# switch.net
KiCad netlist of a schematic drawn in Altium Designer
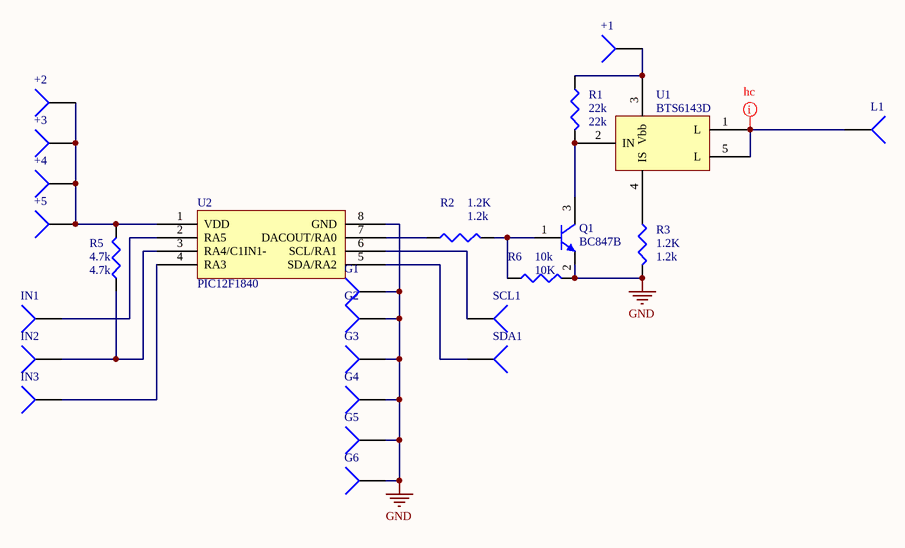
[diagram p0: switch.SchDoc]

(export (version "E")
  (design (tool "Eeschema 10.0.6"))
  (components
    (comp (ref "+1")
      (value "Socket")
      (footprint "PIN1")
      (fields (field (name "PUBLISHER") "Altium Limited"))
      (libsource (lib "misc") (part "Socket"))
    )
    (comp (ref "+2")
      (value "Socket")
      (footprint "PIN1L")
      (fields (field (name "PUBLISHER") "Altium Limited"))
      (libsource (lib "misc") (part "Socket"))
    )
    (comp (ref "+3")
      (value "Socket")
      (footprint "PIN1L")
      (fields (field (name "PUBLISHER") "Altium Limited"))
      (libsource (lib "misc") (part "Socket"))
    )
    (comp (ref "+4")
      (value "Socket")
      (footprint "PIN1L")
      (fields (field (name "PUBLISHER") "Altium Limited"))
      (libsource (lib "misc") (part "Socket"))
    )
    (comp (ref "+5")
      (value "Socket")
      (footprint "PIN1L")
      (fields (field (name "PUBLISHER") "Altium Limited"))
      (libsource (lib "misc") (part "Socket"))
    )
    (comp (ref "G1")
      (value "Socket")
      (footprint "PIN1L")
      (fields (field (name "PUBLISHER") "Altium Limited"))
      (libsource (lib "misc") (part "Socket"))
    )
    (comp (ref "G2")
      (value "Socket")
      (footprint "PIN1L")
      (fields (field (name "PUBLISHER") "Altium Limited"))
      (libsource (lib "misc") (part "Socket"))
    )
    (comp (ref "G3")
      (value "Socket")
      (footprint "PIN1L")
      (fields (field (name "PUBLISHER") "Altium Limited"))
      (libsource (lib "misc") (part "Socket"))
    )
    (comp (ref "G4")
      (value "Socket")
      (footprint "PIN1L")
      (fields (field (name "PUBLISHER") "Altium Limited"))
      (libsource (lib "misc") (part "Socket"))
    )
    (comp (ref "G5")
      (value "Socket")
      (footprint "PIN1")
      (fields (field (name "PUBLISHER") "Altium Limited"))
      (libsource (lib "misc") (part "Socket"))
    )
    (comp (ref "G6")
      (value "Socket")
      (footprint "PIN1")
      (fields (field (name "PUBLISHER") "Altium Limited"))
      (libsource (lib "misc") (part "Socket"))
    )
    (comp (ref "IN1")
      (value "Socket")
      (footprint "PIN1L")
      (fields (field (name "PUBLISHER") "Altium Limited"))
      (libsource (lib "misc") (part "Socket"))
    )
    (comp (ref "IN2")
      (value "Socket")
      (footprint "PIN1L")
      (fields (field (name "PUBLISHER") "Altium Limited"))
      (libsource (lib "misc") (part "Socket"))
    )
    (comp (ref "IN3")
      (value "Socket")
      (footprint "PIN1L")
      (fields (field (name "PUBLISHER") "Altium Limited"))
      (libsource (lib "misc") (part "Socket"))
    )
    (comp (ref "L1")
      (value "Socket")
      (footprint "PIN1")
      (fields (field (name "PUBLISHER") "Altium Limited"))
      (libsource (lib "misc") (part "Socket"))
    )
    (comp (ref "Q1")
      (value "BC847B")
      (footprint "SOT-23_N")
      (description "NPN Bipolar Transistor")
      (fields (field (name "PUBLISHER") "Altium Limited"))
      (libsource (lib "Miscellaneous Devices") (part "NPN"))
    )
    (comp (ref "R1")
      (value "22k")
      (footprint "J1-0603")
      (description "Resistor")
      (fields (field (name "ALTIUM_VALUE") "22k") (field (name "PUBLISHER") "Altium Limited"))
      (libsource (lib "Miscellaneous Devices") (part "Res3"))
    )
    (comp (ref "R2")
      (value "1.2k")
      (footprint "J1-0603")
      (description "Resistor")
      (fields (field (name "ALTIUM_VALUE") "1.2K") (field (name "PUBLISHER") "Altium Limited"))
      (libsource (lib "Miscellaneous Devices") (part "Res3"))
    )
    (comp (ref "R3")
      (value "1.2k")
      (footprint "J1-0603")
      (description "Resistor")
      (fields (field (name "ALTIUM_VALUE") "1.2K") (field (name "PUBLISHER") "Altium Limited"))
      (libsource (lib "Miscellaneous Devices") (part "Res3"))
    )
    (comp (ref "R5")
      (value "4.7k")
      (footprint "J1-0603")
      (description "Resistor")
      (fields (field (name "ALTIUM_VALUE") "4.7k") (field (name "PUBLISHER") "Altium Limited"))
      (libsource (lib "Miscellaneous Devices") (part "Res3"))
    )
    (comp (ref "R6")
      (value "10k")
      (footprint "J1-0603")
      (description "Resistor")
      (fields (field (name "ALTIUM_VALUE") "10K") (field (name "PUBLISHER") "Altium Limited"))
      (libsource (lib "Miscellaneous Devices") (part "Res3"))
    )
    (comp (ref "SCL1")
      (value "Socket")
      (footprint "PIN1L")
      (fields (field (name "PUBLISHER") "Altium Limited"))
      (libsource (lib "misc") (part "Socket"))
    )
    (comp (ref "SDA1")
      (value "Socket")
      (footprint "PIN1L")
      (fields (field (name "PUBLISHER") "Altium Limited"))
      (libsource (lib "misc") (part "Socket"))
    )
    (comp (ref "U1") (value "BTS6143D") (footprint "BTS6143D") (libsource (lib "misc") (part "BTS6143D")))
    (comp (ref "U2")
      (value "PIC12F1840")
      (footprint "SOIC150-8_N")
      (libsource (lib "pic") (part "PIC12F1840"))
    )
  )
  (nets
    (net (code "1") (name "GND") (class "Default")
      (node (ref "G1") (pin "1") (pinfunction "1_1") (pintype "passive"))
      (node (ref "G2") (pin "1") (pinfunction "1_1") (pintype "passive"))
      (node (ref "G3") (pin "1") (pinfunction "1_1") (pintype "passive"))
      (node (ref "G4") (pin "1") (pinfunction "1_1") (pintype "passive"))
      (node (ref "G5") (pin "1") (pinfunction "1_1") (pintype "passive"))
      (node (ref "G6") (pin "1") (pinfunction "1_1") (pintype "passive"))
      (node (ref "Q1") (pin "2") (pinfunction "E_2") (pintype "passive"))
      (node (ref "R3") (pin "2") (pinfunction "2_2") (pintype "passive"))
      (node (ref "R6") (pin "2") (pinfunction "2_2") (pintype "passive"))
      (node (ref "U2") (pin "8") (pinfunction "GND_8") (pintype "passive"))
    )
    (net (code "2") (name "Net-(L1-Pad1)") (class "Default")
      (node (ref "L1") (pin "1") (pinfunction "1_1") (pintype "passive"))
      (node (ref "U1") (pin "1") (pinfunction "L_1") (pintype "passive"))
      (node (ref "U1") (pin "5") (pinfunction "L_5") (pintype "passive"))
    )
    (net (code "3") (name "Net-(Q1-B)") (class "Default")
      (node (ref "Q1") (pin "1") (pinfunction "B_1") (pintype "passive"))
      (node (ref "R2") (pin "2") (pinfunction "2_2") (pintype "passive"))
      (node (ref "R6") (pin "1") (pinfunction "1_1") (pintype "passive"))
    )
    (net (code "4") (name "Net-(Q1-C)") (class "Default")
      (node (ref "Q1") (pin "3") (pinfunction "C_3") (pintype "passive"))
      (node (ref "R1") (pin "2") (pinfunction "2_2") (pintype "passive"))
      (node (ref "U1") (pin "2") (pinfunction "IN_2") (pintype "passive"))
    )
    (net (code "5") (name "Net-(U1-IS)") (class "Default")
      (node (ref "R3") (pin "1") (pinfunction "1_1") (pintype "passive"))
      (node (ref "U1") (pin "4") (pinfunction "IS_4") (pintype "passive"))
    )
    (net (code "6") (name "Net-(U1-Vbb)") (class "Default")
      (node (ref "+1") (pin "1") (pinfunction "1_1") (pintype "passive"))
      (node (ref "R1") (pin "1") (pinfunction "1_1") (pintype "passive"))
      (node (ref "U1") (pin "3") (pinfunction "Vbb_3") (pintype "passive"))
    )
    (net (code "7") (name "Net-(U2-DACOUT{slash}RA0)") (class "Default")
      (node (ref "R2") (pin "1") (pinfunction "1_1") (pintype "passive"))
      (node (ref "U2") (pin "7") (pinfunction "DACOUT/RA0_7") (pintype "passive"))
    )
    (net (code "8") (name "Net-(U2-RA3)") (class "Default")
      (node (ref "IN3") (pin "1") (pinfunction "1_1") (pintype "passive"))
      (node (ref "U2") (pin "4") (pinfunction "RA3_4") (pintype "passive"))
    )
    (net (code "9") (name "Net-(U2-RA4{slash}C1IN1-)") (class "Default")
      (node (ref "IN2") (pin "1") (pinfunction "1_1") (pintype "passive"))
      (node (ref "R5") (pin "1") (pinfunction "1_1") (pintype "passive"))
      (node (ref "U2") (pin "3") (pinfunction "RA4/C1IN1-_3") (pintype "passive"))
    )
    (net (code "10") (name "Net-(U2-RA5)") (class "Default")
      (node (ref "IN1") (pin "1") (pinfunction "1_1") (pintype "passive"))
      (node (ref "U2") (pin "2") (pinfunction "RA5_2") (pintype "passive"))
    )
    (net (code "11") (name "Net-(U2-SCL{slash}RA1)") (class "Default")
      (node (ref "SCL1") (pin "1") (pinfunction "1_1") (pintype "passive"))
      (node (ref "U2") (pin "6") (pinfunction "SCL/RA1_6") (pintype "passive"))
    )
    (net (code "12") (name "Net-(U2-SDA{slash}RA2)") (class "Default")
      (node (ref "SDA1") (pin "1") (pinfunction "1_1") (pintype "passive"))
      (node (ref "U2") (pin "5") (pinfunction "SDA/RA2_5") (pintype "passive"))
    )
    (net (code "13") (name "Net-(U2-VDD)") (class "Default")
      (node (ref "+2") (pin "1") (pinfunction "1_1") (pintype "passive"))
      (node (ref "+3") (pin "1") (pinfunction "1_1") (pintype "passive"))
      (node (ref "+4") (pin "1") (pinfunction "1_1") (pintype "passive"))
      (node (ref "+5") (pin "1") (pinfunction "1_1") (pintype "passive"))
      (node (ref "R5") (pin "2") (pinfunction "2_2") (pintype "passive"))
      (node (ref "U2") (pin "1") (pinfunction "VDD_1") (pintype "passive"))
    )
  )
)
